# BATT_DISP_v6.net
KiCad netlist of a schematic drawn in EAGLE
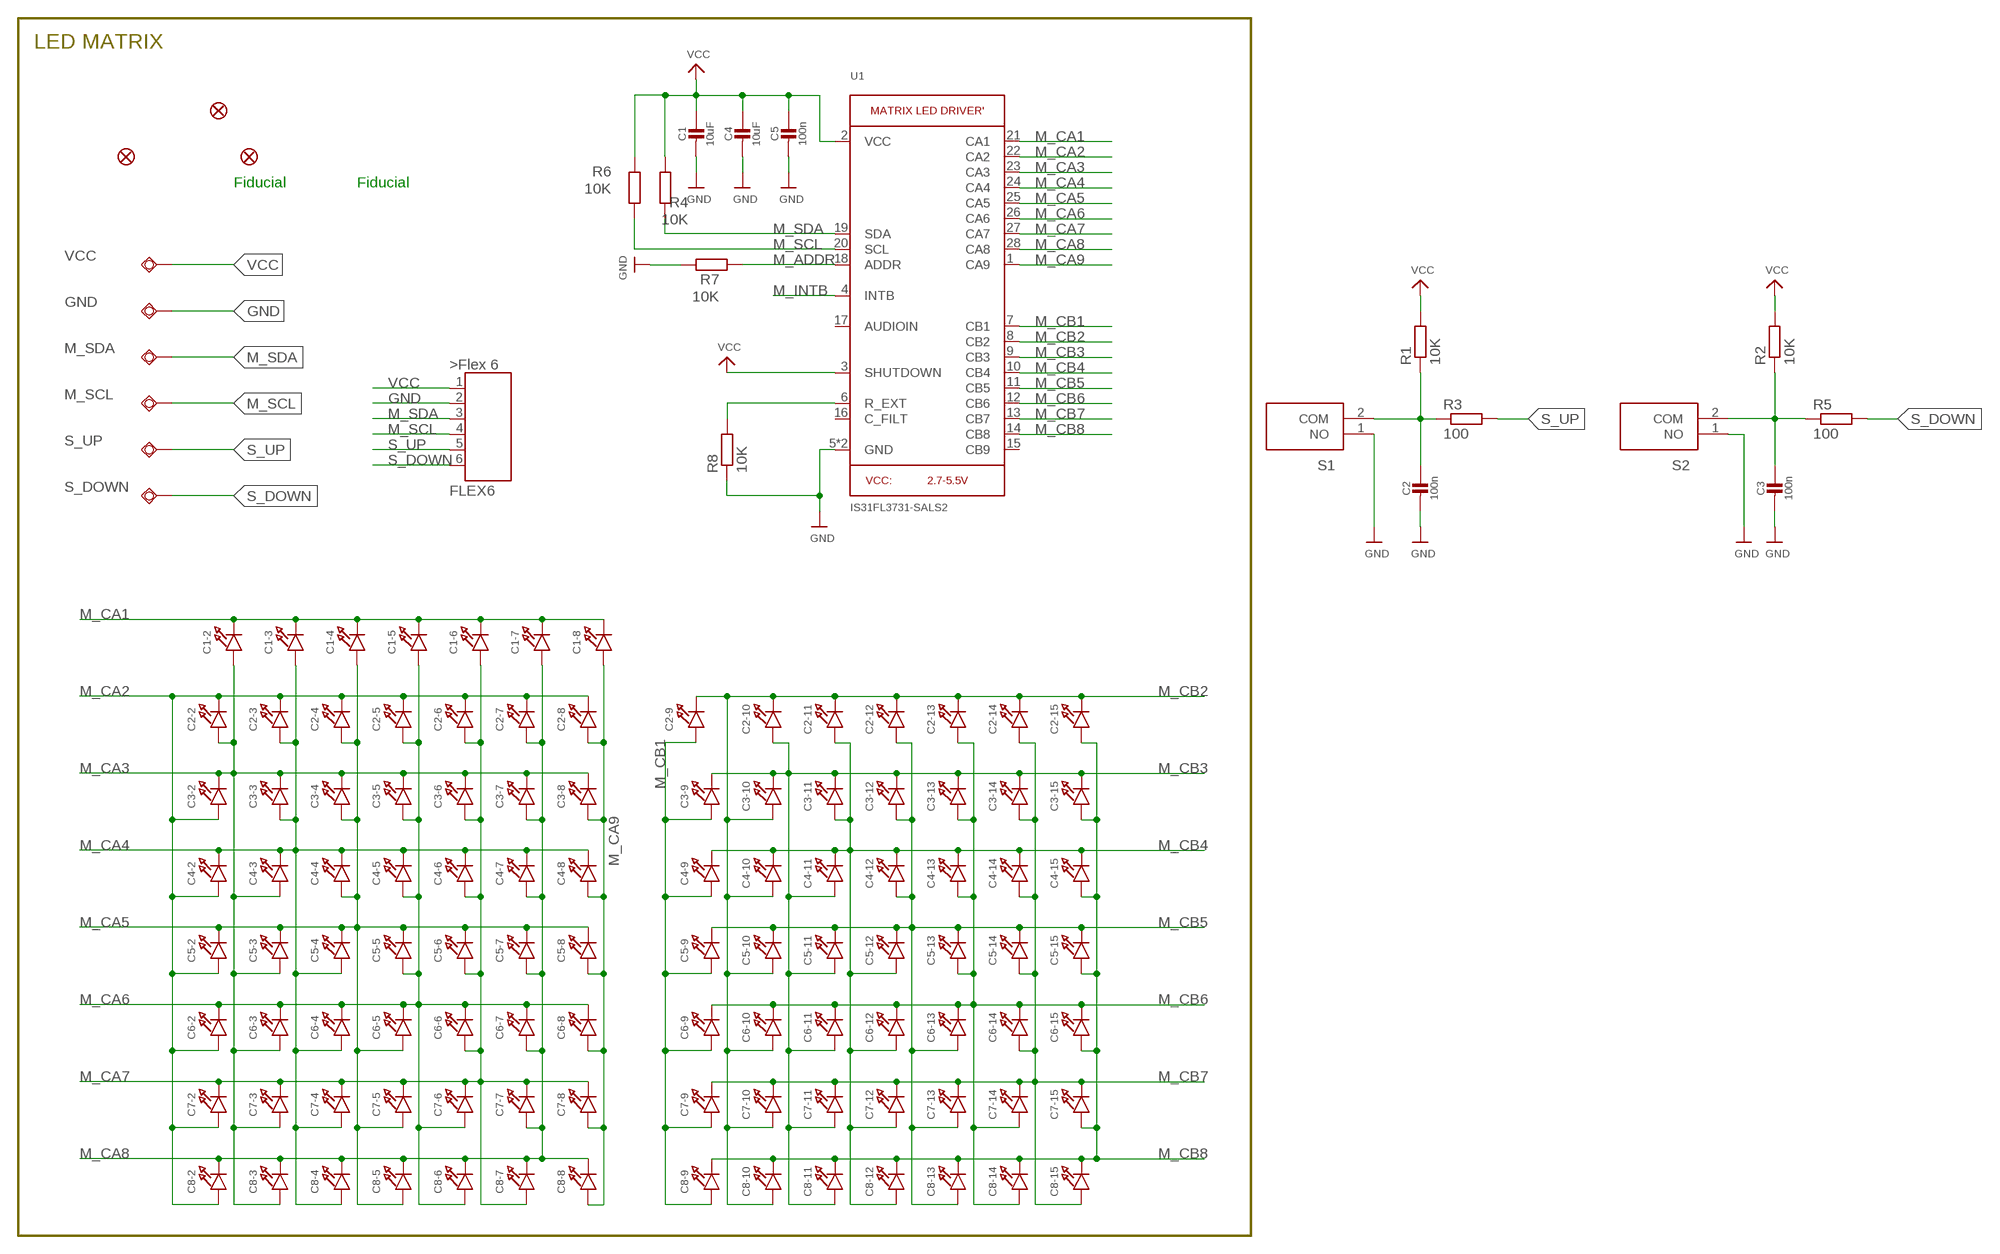
[diagram p0: schematic, sheet 1]

(export (version "E")
  (design (tool "Eeschema 10.0.6"))
  (components
    (comp (ref "C1")
      (value "10uF")
      (footprint "eagle-import:0805-NO")
      (libsource (lib "eagle-import") (part "CAP_CERAMIC0805-NOOUTLINE"))
    )
    (comp (ref "C1-2")
      (value "LED0402_NOOUTLINE")
      (footprint "eagle-import:CHIPLED_0402_NOOUTLINE")
      (libsource (lib "eagle-import") (part "LED0402_NOOUTLINE"))
    )
    (comp (ref "C1-3")
      (value "LED0402_NOOUTLINE")
      (footprint "eagle-import:CHIPLED_0402_NOOUTLINE")
      (libsource (lib "eagle-import") (part "LED0402_NOOUTLINE"))
    )
    (comp (ref "C1-4")
      (value "LED0402_NOOUTLINE")
      (footprint "eagle-import:CHIPLED_0402_NOOUTLINE")
      (libsource (lib "eagle-import") (part "LED0402_NOOUTLINE"))
    )
    (comp (ref "C1-5")
      (value "LED0402_NOOUTLINE")
      (footprint "eagle-import:CHIPLED_0402_NOOUTLINE")
      (libsource (lib "eagle-import") (part "LED0402_NOOUTLINE"))
    )
    (comp (ref "C1-6")
      (value "LED0402_NOOUTLINE")
      (footprint "eagle-import:CHIPLED_0402_NOOUTLINE")
      (libsource (lib "eagle-import") (part "LED0402_NOOUTLINE"))
    )
    (comp (ref "C1-7")
      (value "LED0402_NOOUTLINE")
      (footprint "eagle-import:CHIPLED_0402_NOOUTLINE")
      (libsource (lib "eagle-import") (part "LED0402_NOOUTLINE"))
    )
    (comp (ref "C1-8")
      (value "LED0402_NOOUTLINE")
      (footprint "eagle-import:CHIPLED_0402_NOOUTLINE")
      (libsource (lib "eagle-import") (part "LED0402_NOOUTLINE"))
    )
    (comp (ref "C2")
      (value "100n")
      (footprint "eagle-import:0805-NO")
      (libsource (lib "eagle-import") (part "CAP_CERAMIC0805-NOOUTLINE"))
    )
    (comp (ref "C2-2")
      (value "LED0402_NOOUTLINE")
      (footprint "eagle-import:CHIPLED_0402_NOOUTLINE")
      (libsource (lib "eagle-import") (part "LED0402_NOOUTLINE"))
    )
    (comp (ref "C2-3")
      (value "LED0402_NOOUTLINE")
      (footprint "eagle-import:CHIPLED_0402_NOOUTLINE")
      (libsource (lib "eagle-import") (part "LED0402_NOOUTLINE"))
    )
    (comp (ref "C2-4")
      (value "LED0402_NOOUTLINE")
      (footprint "eagle-import:CHIPLED_0402_NOOUTLINE")
      (libsource (lib "eagle-import") (part "LED0402_NOOUTLINE"))
    )
    (comp (ref "C2-5")
      (value "LED0402_NOOUTLINE")
      (footprint "eagle-import:CHIPLED_0402_NOOUTLINE")
      (libsource (lib "eagle-import") (part "LED0402_NOOUTLINE"))
    )
    (comp (ref "C2-6")
      (value "LED0402_NOOUTLINE")
      (footprint "eagle-import:CHIPLED_0402_NOOUTLINE")
      (libsource (lib "eagle-import") (part "LED0402_NOOUTLINE"))
    )
    (comp (ref "C2-7")
      (value "LED0402_NOOUTLINE")
      (footprint "eagle-import:CHIPLED_0402_NOOUTLINE")
      (libsource (lib "eagle-import") (part "LED0402_NOOUTLINE"))
    )
    (comp (ref "C2-8")
      (value "LED0402_NOOUTLINE")
      (footprint "eagle-import:CHIPLED_0402_NOOUTLINE")
      (libsource (lib "eagle-import") (part "LED0402_NOOUTLINE"))
    )
    (comp (ref "C2-9")
      (value "LED0402_NOOUTLINE")
      (footprint "eagle-import:CHIPLED_0402_NOOUTLINE")
      (libsource (lib "eagle-import") (part "LED0402_NOOUTLINE"))
    )
    (comp (ref "C2-10")
      (value "LED0402_NOOUTLINE")
      (footprint "eagle-import:CHIPLED_0402_NOOUTLINE")
      (libsource (lib "eagle-import") (part "LED0402_NOOUTLINE"))
    )
    (comp (ref "C2-11")
      (value "LED0402_NOOUTLINE")
      (footprint "eagle-import:CHIPLED_0402_NOOUTLINE")
      (libsource (lib "eagle-import") (part "LED0402_NOOUTLINE"))
    )
    (comp (ref "C2-12")
      (value "LED0402_NOOUTLINE")
      (footprint "eagle-import:CHIPLED_0402_NOOUTLINE")
      (libsource (lib "eagle-import") (part "LED0402_NOOUTLINE"))
    )
    (comp (ref "C2-13")
      (value "LED0402_NOOUTLINE")
      (footprint "eagle-import:CHIPLED_0402_NOOUTLINE")
      (libsource (lib "eagle-import") (part "LED0402_NOOUTLINE"))
    )
    (comp (ref "C2-14")
      (value "LED0402_NOOUTLINE")
      (footprint "eagle-import:CHIPLED_0402_NOOUTLINE")
      (libsource (lib "eagle-import") (part "LED0402_NOOUTLINE"))
    )
    (comp (ref "C2-15")
      (value "LED0402_NOOUTLINE")
      (footprint "eagle-import:CHIPLED_0402_NOOUTLINE")
      (libsource (lib "eagle-import") (part "LED0402_NOOUTLINE"))
    )
    (comp (ref "C3")
      (value "100n")
      (footprint "eagle-import:0805-NO")
      (libsource (lib "eagle-import") (part "CAP_CERAMIC0805-NOOUTLINE"))
    )
    (comp (ref "C3-2")
      (value "LED0402_NOOUTLINE")
      (footprint "eagle-import:CHIPLED_0402_NOOUTLINE")
      (libsource (lib "eagle-import") (part "LED0402_NOOUTLINE"))
    )
    (comp (ref "C3-3")
      (value "LED0402_NOOUTLINE")
      (footprint "eagle-import:CHIPLED_0402_NOOUTLINE")
      (libsource (lib "eagle-import") (part "LED0402_NOOUTLINE"))
    )
    (comp (ref "C3-4")
      (value "LED0402_NOOUTLINE")
      (footprint "eagle-import:CHIPLED_0402_NOOUTLINE")
      (libsource (lib "eagle-import") (part "LED0402_NOOUTLINE"))
    )
    (comp (ref "C3-5")
      (value "LED0402_NOOUTLINE")
      (footprint "eagle-import:CHIPLED_0402_NOOUTLINE")
      (libsource (lib "eagle-import") (part "LED0402_NOOUTLINE"))
    )
    (comp (ref "C3-6")
      (value "LED0402_NOOUTLINE")
      (footprint "eagle-import:CHIPLED_0402_NOOUTLINE")
      (libsource (lib "eagle-import") (part "LED0402_NOOUTLINE"))
    )
    (comp (ref "C3-7")
      (value "LED0402_NOOUTLINE")
      (footprint "eagle-import:CHIPLED_0402_NOOUTLINE")
      (libsource (lib "eagle-import") (part "LED0402_NOOUTLINE"))
    )
    (comp (ref "C3-8")
      (value "LED0402_NOOUTLINE")
      (footprint "eagle-import:CHIPLED_0402_NOOUTLINE")
      (libsource (lib "eagle-import") (part "LED0402_NOOUTLINE"))
    )
    (comp (ref "C3-9")
      (value "LED0402_NOOUTLINE")
      (footprint "eagle-import:CHIPLED_0402_NOOUTLINE")
      (libsource (lib "eagle-import") (part "LED0402_NOOUTLINE"))
    )
    (comp (ref "C3-10")
      (value "LED0402_NOOUTLINE")
      (footprint "eagle-import:CHIPLED_0402_NOOUTLINE")
      (libsource (lib "eagle-import") (part "LED0402_NOOUTLINE"))
    )
    (comp (ref "C3-11")
      (value "LED0402_NOOUTLINE")
      (footprint "eagle-import:CHIPLED_0402_NOOUTLINE")
      (libsource (lib "eagle-import") (part "LED0402_NOOUTLINE"))
    )
    (comp (ref "C3-12")
      (value "LED0402_NOOUTLINE")
      (footprint "eagle-import:CHIPLED_0402_NOOUTLINE")
      (libsource (lib "eagle-import") (part "LED0402_NOOUTLINE"))
    )
    (comp (ref "C3-13")
      (value "LED0402_NOOUTLINE")
      (footprint "eagle-import:CHIPLED_0402_NOOUTLINE")
      (libsource (lib "eagle-import") (part "LED0402_NOOUTLINE"))
    )
    (comp (ref "C3-14")
      (value "LED0402_NOOUTLINE")
      (footprint "eagle-import:CHIPLED_0402_NOOUTLINE")
      (libsource (lib "eagle-import") (part "LED0402_NOOUTLINE"))
    )
    (comp (ref "C3-15")
      (value "LED0402_NOOUTLINE")
      (footprint "eagle-import:CHIPLED_0402_NOOUTLINE")
      (libsource (lib "eagle-import") (part "LED0402_NOOUTLINE"))
    )
    (comp (ref "C4")
      (value "10uF")
      (footprint "eagle-import:0805-NO")
      (libsource (lib "eagle-import") (part "CAP_CERAMIC0805-NOOUTLINE"))
    )
    (comp (ref "C4-2")
      (value "LED0402_NOOUTLINE")
      (footprint "eagle-import:CHIPLED_0402_NOOUTLINE")
      (libsource (lib "eagle-import") (part "LED0402_NOOUTLINE"))
    )
    (comp (ref "C4-3")
      (value "LED0402_NOOUTLINE")
      (footprint "eagle-import:CHIPLED_0402_NOOUTLINE")
      (libsource (lib "eagle-import") (part "LED0402_NOOUTLINE"))
    )
    (comp (ref "C4-4")
      (value "LED0402_NOOUTLINE")
      (footprint "eagle-import:CHIPLED_0402_NOOUTLINE")
      (libsource (lib "eagle-import") (part "LED0402_NOOUTLINE"))
    )
    (comp (ref "C4-5")
      (value "LED0402_NOOUTLINE")
      (footprint "eagle-import:CHIPLED_0402_NOOUTLINE")
      (libsource (lib "eagle-import") (part "LED0402_NOOUTLINE"))
    )
    (comp (ref "C4-6")
      (value "LED0402_NOOUTLINE")
      (footprint "eagle-import:CHIPLED_0402_NOOUTLINE")
      (libsource (lib "eagle-import") (part "LED0402_NOOUTLINE"))
    )
    (comp (ref "C4-7")
      (value "LED0402_NOOUTLINE")
      (footprint "eagle-import:CHIPLED_0402_NOOUTLINE")
      (libsource (lib "eagle-import") (part "LED0402_NOOUTLINE"))
    )
    (comp (ref "C4-8")
      (value "LED0402_NOOUTLINE")
      (footprint "eagle-import:CHIPLED_0402_NOOUTLINE")
      (libsource (lib "eagle-import") (part "LED0402_NOOUTLINE"))
    )
    (comp (ref "C4-9")
      (value "LED0402_NOOUTLINE")
      (footprint "eagle-import:CHIPLED_0402_NOOUTLINE")
      (libsource (lib "eagle-import") (part "LED0402_NOOUTLINE"))
    )
    (comp (ref "C4-10")
      (value "LED0402_NOOUTLINE")
      (footprint "eagle-import:CHIPLED_0402_NOOUTLINE")
      (libsource (lib "eagle-import") (part "LED0402_NOOUTLINE"))
    )
    (comp (ref "C4-11")
      (value "LED0402_NOOUTLINE")
      (footprint "eagle-import:CHIPLED_0402_NOOUTLINE")
      (libsource (lib "eagle-import") (part "LED0402_NOOUTLINE"))
    )
    (comp (ref "C4-12")
      (value "LED0402_NOOUTLINE")
      (footprint "eagle-import:CHIPLED_0402_NOOUTLINE")
      (libsource (lib "eagle-import") (part "LED0402_NOOUTLINE"))
    )
    (comp (ref "C4-13")
      (value "LED0402_NOOUTLINE")
      (footprint "eagle-import:CHIPLED_0402_NOOUTLINE")
      (libsource (lib "eagle-import") (part "LED0402_NOOUTLINE"))
    )
    (comp (ref "C4-14")
      (value "LED0402_NOOUTLINE")
      (footprint "eagle-import:CHIPLED_0402_NOOUTLINE")
      (libsource (lib "eagle-import") (part "LED0402_NOOUTLINE"))
    )
    (comp (ref "C4-15")
      (value "LED0402_NOOUTLINE")
      (footprint "eagle-import:CHIPLED_0402_NOOUTLINE")
      (libsource (lib "eagle-import") (part "LED0402_NOOUTLINE"))
    )
    (comp (ref "C5")
      (value "100n")
      (footprint "eagle-import:0805-NO")
      (libsource (lib "eagle-import") (part "CAP_CERAMIC0805-NOOUTLINE"))
    )
    (comp (ref "C5-2")
      (value "LED0402_NOOUTLINE")
      (footprint "eagle-import:CHIPLED_0402_NOOUTLINE")
      (libsource (lib "eagle-import") (part "LED0402_NOOUTLINE"))
    )
    (comp (ref "C5-3")
      (value "LED0402_NOOUTLINE")
      (footprint "eagle-import:CHIPLED_0402_NOOUTLINE")
      (libsource (lib "eagle-import") (part "LED0402_NOOUTLINE"))
    )
    (comp (ref "C5-4")
      (value "LED0402_NOOUTLINE")
      (footprint "eagle-import:CHIPLED_0402_NOOUTLINE")
      (libsource (lib "eagle-import") (part "LED0402_NOOUTLINE"))
    )
    (comp (ref "C5-5")
      (value "LED0402_NOOUTLINE")
      (footprint "eagle-import:CHIPLED_0402_NOOUTLINE")
      (libsource (lib "eagle-import") (part "LED0402_NOOUTLINE"))
    )
    (comp (ref "C5-6")
      (value "LED0402_NOOUTLINE")
      (footprint "eagle-import:CHIPLED_0402_NOOUTLINE")
      (libsource (lib "eagle-import") (part "LED0402_NOOUTLINE"))
    )
    (comp (ref "C5-7")
      (value "LED0402_NOOUTLINE")
      (footprint "eagle-import:CHIPLED_0402_NOOUTLINE")
      (libsource (lib "eagle-import") (part "LED0402_NOOUTLINE"))
    )
    (comp (ref "C5-8")
      (value "LED0402_NOOUTLINE")
      (footprint "eagle-import:CHIPLED_0402_NOOUTLINE")
      (libsource (lib "eagle-import") (part "LED0402_NOOUTLINE"))
    )
    (comp (ref "C5-9")
      (value "LED0402_NOOUTLINE")
      (footprint "eagle-import:CHIPLED_0402_NOOUTLINE")
      (libsource (lib "eagle-import") (part "LED0402_NOOUTLINE"))
    )
    (comp (ref "C5-10")
      (value "LED0402_NOOUTLINE")
      (footprint "eagle-import:CHIPLED_0402_NOOUTLINE")
      (libsource (lib "eagle-import") (part "LED0402_NOOUTLINE"))
    )
    (comp (ref "C5-11")
      (value "LED0402_NOOUTLINE")
      (footprint "eagle-import:CHIPLED_0402_NOOUTLINE")
      (libsource (lib "eagle-import") (part "LED0402_NOOUTLINE"))
    )
    (comp (ref "C5-12")
      (value "LED0402_NOOUTLINE")
      (footprint "eagle-import:CHIPLED_0402_NOOUTLINE")
      (libsource (lib "eagle-import") (part "LED0402_NOOUTLINE"))
    )
    (comp (ref "C5-13")
      (value "LED0402_NOOUTLINE")
      (footprint "eagle-import:CHIPLED_0402_NOOUTLINE")
      (libsource (lib "eagle-import") (part "LED0402_NOOUTLINE"))
    )
    (comp (ref "C5-14")
      (value "LED0402_NOOUTLINE")
      (footprint "eagle-import:CHIPLED_0402_NOOUTLINE")
      (libsource (lib "eagle-import") (part "LED0402_NOOUTLINE"))
    )
    (comp (ref "C5-15")
      (value "LED0402_NOOUTLINE")
      (footprint "eagle-import:CHIPLED_0402_NOOUTLINE")
      (libsource (lib "eagle-import") (part "LED0402_NOOUTLINE"))
    )
    (comp (ref "C6-2")
      (value "LED0402_NOOUTLINE")
      (footprint "eagle-import:CHIPLED_0402_NOOUTLINE")
      (libsource (lib "eagle-import") (part "LED0402_NOOUTLINE"))
    )
    (comp (ref "C6-3")
      (value "LED0402_NOOUTLINE")
      (footprint "eagle-import:CHIPLED_0402_NOOUTLINE")
      (libsource (lib "eagle-import") (part "LED0402_NOOUTLINE"))
    )
    (comp (ref "C6-4")
      (value "LED0402_NOOUTLINE")
      (footprint "eagle-import:CHIPLED_0402_NOOUTLINE")
      (libsource (lib "eagle-import") (part "LED0402_NOOUTLINE"))
    )
    (comp (ref "C6-5")
      (value "LED0402_NOOUTLINE")
      (footprint "eagle-import:CHIPLED_0402_NOOUTLINE")
      (libsource (lib "eagle-import") (part "LED0402_NOOUTLINE"))
    )
    (comp (ref "C6-6")
      (value "LED0402_NOOUTLINE")
      (footprint "eagle-import:CHIPLED_0402_NOOUTLINE")
      (libsource (lib "eagle-import") (part "LED0402_NOOUTLINE"))
    )
    (comp (ref "C6-7")
      (value "LED0402_NOOUTLINE")
      (footprint "eagle-import:CHIPLED_0402_NOOUTLINE")
      (libsource (lib "eagle-import") (part "LED0402_NOOUTLINE"))
    )
    (comp (ref "C6-8")
      (value "LED0402_NOOUTLINE")
      (footprint "eagle-import:CHIPLED_0402_NOOUTLINE")
      (libsource (lib "eagle-import") (part "LED0402_NOOUTLINE"))
    )
    (comp (ref "C6-9")
      (value "LED0402_NOOUTLINE")
      (footprint "eagle-import:CHIPLED_0402_NOOUTLINE")
      (libsource (lib "eagle-import") (part "LED0402_NOOUTLINE"))
    )
    (comp (ref "C6-10")
      (value "LED0402_NOOUTLINE")
      (footprint "eagle-import:CHIPLED_0402_NOOUTLINE")
      (libsource (lib "eagle-import") (part "LED0402_NOOUTLINE"))
    )
    (comp (ref "C6-11")
      (value "LED0402_NOOUTLINE")
      (footprint "eagle-import:CHIPLED_0402_NOOUTLINE")
      (libsource (lib "eagle-import") (part "LED0402_NOOUTLINE"))
    )
    (comp (ref "C6-12")
      (value "LED0402_NOOUTLINE")
      (footprint "eagle-import:CHIPLED_0402_NOOUTLINE")
      (libsource (lib "eagle-import") (part "LED0402_NOOUTLINE"))
    )
    (comp (ref "C6-13")
      (value "LED0402_NOOUTLINE")
      (footprint "eagle-import:CHIPLED_0402_NOOUTLINE")
      (libsource (lib "eagle-import") (part "LED0402_NOOUTLINE"))
    )
    (comp (ref "C6-14")
      (value "LED0402_NOOUTLINE")
      (footprint "eagle-import:CHIPLED_0402_NOOUTLINE")
      (libsource (lib "eagle-import") (part "LED0402_NOOUTLINE"))
    )
    (comp (ref "C6-15")
      (value "LED0402_NOOUTLINE")
      (footprint "eagle-import:CHIPLED_0402_NOOUTLINE")
      (libsource (lib "eagle-import") (part "LED0402_NOOUTLINE"))
    )
    (comp (ref "C7-2")
      (value "LED0402_NOOUTLINE")
      (footprint "eagle-import:CHIPLED_0402_NOOUTLINE")
      (libsource (lib "eagle-import") (part "LED0402_NOOUTLINE"))
    )
    (comp (ref "C7-3")
      (value "LED0402_NOOUTLINE")
      (footprint "eagle-import:CHIPLED_0402_NOOUTLINE")
      (libsource (lib "eagle-import") (part "LED0402_NOOUTLINE"))
    )
    (comp (ref "C7-4")
      (value "LED0402_NOOUTLINE")
      (footprint "eagle-import:CHIPLED_0402_NOOUTLINE")
      (libsource (lib "eagle-import") (part "LED0402_NOOUTLINE"))
    )
    (comp (ref "C7-5")
      (value "LED0402_NOOUTLINE")
      (footprint "eagle-import:CHIPLED_0402_NOOUTLINE")
      (libsource (lib "eagle-import") (part "LED0402_NOOUTLINE"))
    )
    (comp (ref "C7-6")
      (value "LED0402_NOOUTLINE")
      (footprint "eagle-import:CHIPLED_0402_NOOUTLINE")
      (libsource (lib "eagle-import") (part "LED0402_NOOUTLINE"))
    )
    (comp (ref "C7-7")
      (value "LED0402_NOOUTLINE")
      (footprint "eagle-import:CHIPLED_0402_NOOUTLINE")
      (libsource (lib "eagle-import") (part "LED0402_NOOUTLINE"))
    )
    (comp (ref "C7-8")
      (value "LED0402_NOOUTLINE")
      (footprint "eagle-import:CHIPLED_0402_NOOUTLINE")
      (libsource (lib "eagle-import") (part "LED0402_NOOUTLINE"))
    )
    (comp (ref "C7-9")
      (value "LED0402_NOOUTLINE")
      (footprint "eagle-import:CHIPLED_0402_NOOUTLINE")
      (libsource (lib "eagle-import") (part "LED0402_NOOUTLINE"))
    )
    (comp (ref "C7-10")
      (value "LED0402_NOOUTLINE")
      (footprint "eagle-import:CHIPLED_0402_NOOUTLINE")
      (libsource (lib "eagle-import") (part "LED0402_NOOUTLINE"))
    )
    (comp (ref "C7-11")
      (value "LED0402_NOOUTLINE")
      (footprint "eagle-import:CHIPLED_0402_NOOUTLINE")
      (libsource (lib "eagle-import") (part "LED0402_NOOUTLINE"))
    )
    (comp (ref "C7-12")
      (value "LED0402_NOOUTLINE")
      (footprint "eagle-import:CHIPLED_0402_NOOUTLINE")
      (libsource (lib "eagle-import") (part "LED0402_NOOUTLINE"))
    )
    (comp (ref "C7-13")
      (value "LED0402_NOOUTLINE")
      (footprint "eagle-import:CHIPLED_0402_NOOUTLINE")
      (libsource (lib "eagle-import") (part "LED0402_NOOUTLINE"))
    )
    (comp (ref "C7-14")
      (value "LED0402_NOOUTLINE")
      (footprint "eagle-import:CHIPLED_0402_NOOUTLINE")
      (libsource (lib "eagle-import") (part "LED0402_NOOUTLINE"))
    )
    (comp (ref "C7-15")
      (value "LED0402_NOOUTLINE")
      (footprint "eagle-import:CHIPLED_0402_NOOUTLINE")
      (libsource (lib "eagle-import") (part "LED0402_NOOUTLINE"))
    )
    (comp (ref "C8-2")
      (value "LED0402_NOOUTLINE")
      (footprint "eagle-import:CHIPLED_0402_NOOUTLINE")
      (libsource (lib "eagle-import") (part "LED0402_NOOUTLINE"))
    )
    (comp (ref "C8-3")
      (value "LED0402_NOOUTLINE")
      (footprint "eagle-import:CHIPLED_0402_NOOUTLINE")
      (libsource (lib "eagle-import") (part "LED0402_NOOUTLINE"))
    )
    (comp (ref "C8-4")
      (value "LED0402_NOOUTLINE")
      (footprint "eagle-import:CHIPLED_0402_NOOUTLINE")
      (libsource (lib "eagle-import") (part "LED0402_NOOUTLINE"))
    )
    (comp (ref "C8-5")
      (value "LED0402_NOOUTLINE")
      (footprint "eagle-import:CHIPLED_0402_NOOUTLINE")
      (libsource (lib "eagle-import") (part "LED0402_NOOUTLINE"))
    )
    (comp (ref "C8-6")
      (value "LED0402_NOOUTLINE")
      (footprint "eagle-import:CHIPLED_0402_NOOUTLINE")
      (libsource (lib "eagle-import") (part "LED0402_NOOUTLINE"))
    )
    (comp (ref "C8-7")
      (value "LED0402_NOOUTLINE")
      (footprint "eagle-import:CHIPLED_0402_NOOUTLINE")
      (libsource (lib "eagle-import") (part "LED0402_NOOUTLINE"))
    )
    (comp (ref "C8-8")
      (value "LED0402_NOOUTLINE")
      (footprint "eagle-import:CHIPLED_0402_NOOUTLINE")
      (libsource (lib "eagle-import") (part "LED0402_NOOUTLINE"))
    )
    (comp (ref "C8-9")
      (value "LED0402_NOOUTLINE")
      (footprint "eagle-import:CHIPLED_0402_NOOUTLINE")
      (libsource (lib "eagle-import") (part "LED0402_NOOUTLINE"))
    )
    (comp (ref "C8-10")
      (value "LED0402_NOOUTLINE")
      (footprint "eagle-import:CHIPLED_0402_NOOUTLINE")
      (libsource (lib "eagle-import") (part "LED0402_NOOUTLINE"))
    )
    (comp (ref "C8-11")
      (value "LED0402_NOOUTLINE")
      (footprint "eagle-import:CHIPLED_0402_NOOUTLINE")
      (libsource (lib "eagle-import") (part "LED0402_NOOUTLINE"))
    )
    (comp (ref "C8-12")
      (value "LED0402_NOOUTLINE")
      (footprint "eagle-import:CHIPLED_0402_NOOUTLINE")
      (libsource (lib "eagle-import") (part "LED0402_NOOUTLINE"))
    )
    (comp (ref "C8-13")
      (value "LED0402_NOOUTLINE")
      (footprint "eagle-import:CHIPLED_0402_NOOUTLINE")
      (libsource (lib "eagle-import") (part "LED0402_NOOUTLINE"))
    )
    (comp (ref "C8-14")
      (value "LED0402_NOOUTLINE")
      (footprint "eagle-import:CHIPLED_0402_NOOUTLINE")
      (libsource (lib "eagle-import") (part "LED0402_NOOUTLINE"))
    )
    (comp (ref "C8-15")
      (value "LED0402_NOOUTLINE")
      (footprint "eagle-import:CHIPLED_0402_NOOUTLINE")
      (libsource (lib "eagle-import") (part "LED0402_NOOUTLINE"))
    )
    (comp (ref "FD1")
      (value "FIDUCIALUFIDUCIAL")
      (footprint "eagle-import:FIDUCIAL-MICRO")
      (libsource (lib "eagle-import") (part "FIDUCIALUFIDUCIAL"))
    )
    (comp (ref "FD2")
      (value "FIDUCIAL\"\"")
      (footprint "eagle-import:FIDUCIAL_1MM")
      (libsource (lib "eagle-import") (part "FIDUCIAL{dblquote}{dblquote}"))
    )
    (comp (ref "FD3")
      (value "FIDUCIAL\"\"")
      (footprint "eagle-import:FIDUCIAL_1MM")
      (libsource (lib "eagle-import") (part "FIDUCIAL{dblquote}{dblquote}"))
    )
    (comp (ref "GND")
      (value "TESTPAD_TPSQB1,27")
      (footprint "eagle-import:TESTPAD_B1,27")
      (libsource (lib "eagle-import") (part "TESTPAD_TPSQB1,27"))
    )
    (comp (ref "K1")
      (value "FLEX6")
      (footprint "eagle-import:FLEX6")
      (libsource (lib "eagle-import") (part "FLEX6"))
    )
    (comp (ref "M_SCL")
      (value "TESTPAD_TPSQB1,27")
      (footprint "eagle-import:TESTPAD_B1,27")
      (libsource (lib "eagle-import") (part "TESTPAD_TPSQB1,27"))
    )
    (comp (ref "M_SDA")
      (value "TESTPAD_TPSQB1,27")
      (footprint "eagle-import:TESTPAD_B1,27")
      (libsource (lib "eagle-import") (part "TESTPAD_TPSQB1,27"))
    )
    (comp (ref "R1")
      (value "10K")
      (footprint "eagle-import:R0603")
      (libsource (lib "eagle-import") (part "R-EU_R0603"))
    )
    (comp (ref "R2")
      (value "10K")
      (footprint "eagle-import:R0603")
      (libsource (lib "eagle-import") (part "R-EU_R0603"))
    )
    (comp (ref "R3")
      (value "100")
      (footprint "eagle-import:R0603")
      (libsource (lib "eagle-import") (part "R-EU_R0603"))
    )
    (comp (ref "R4")
      (value "10K")
      (footprint "eagle-import:R0603")
      (libsource (lib "eagle-import") (part "R-EU_R0603"))
    )
    (comp (ref "R5")
      (value "100")
      (footprint "eagle-import:R0603")
      (libsource (lib "eagle-import") (part "R-EU_R0603"))
    )
    (comp (ref "R6")
      (value "10K")
      (footprint "eagle-import:R0603")
      (libsource (lib "eagle-import") (part "R-EU_R0603"))
    )
    (comp (ref "R7")
      (value "10K")
      (footprint "eagle-import:R0603")
      (libsource (lib "eagle-import") (part "R-EU_R0603"))
    )
    (comp (ref "R8")
      (value "10K")
      (footprint "eagle-import:R0603")
      (libsource (lib "eagle-import") (part "R-EU_R0603"))
    )
    (comp (ref "S1")
      (value "KXT311LHS")
      (footprint "eagle-import:KXT311LHS")
      (fields (field (name "MOUSER_PART_NUMBER") "611-KXT311LHS"))
      (libsource (lib "eagle-import") (part "KXT311LHS"))
    )
    (comp (ref "S2")
      (value "KXT311LHS")
      (footprint "eagle-import:KXT311LHS")
      (fields (field (name "MOUSER_PART_NUMBER") "611-KXT311LHS"))
      (libsource (lib "eagle-import") (part "KXT311LHS"))
    )
    (comp (ref "S_DOWN")
      (value "TESTPAD_TPSQB1,27")
      (footprint "eagle-import:TESTPAD_B1,27")
      (libsource (lib "eagle-import") (part "TESTPAD_TPSQB1,27"))
    )
    (comp (ref "S_UP")
      (value "TESTPAD_TPSQB1,27")
      (footprint "eagle-import:TESTPAD_B1,27")
      (libsource (lib "eagle-import") (part "TESTPAD_TPSQB1,27"))
    )
    (comp (ref "U1")
      (value "IS31FL3731-SALS2")
      (footprint "eagle-import:QFN28_4MM_0.4MM")
      (libsource (lib "eagle-import") (part "IS31FL3731QFN"))
    )
    (comp (ref "VCC")
      (value "TESTPAD_TPSQB1,27")
      (footprint "eagle-import:TESTPAD_B1,27")
      (libsource (lib "eagle-import") (part "TESTPAD_TPSQB1,27"))
    )
  )
  (nets
    (net (code "1") (name "/M_ADDR") (class "Default")
      (node (ref "R7") (pin "1") (pinfunction "1_1") (pintype "passive"))
      (node (ref "U1") (pin "18") (pinfunction "ADDR_18") (pintype "bidirectional"))
    )
    (net (code "2") (name "/M_CA1") (class "Default")
      (node (ref "C1-2") (pin "C") (pinfunction "C_C") (pintype "passive"))
      (node (ref "C1-3") (pin "C") (pinfunction "C_C") (pintype "passive"))
      (node (ref "C1-4") (pin "C") (pinfunction "C_C") (pintype "passive"))
      (node (ref "C1-5") (pin "C") (pinfunction "C_C") (pintype "passive"))
      (node (ref "C1-6") (pin "C") (pinfunction "C_C") (pintype "passive"))
      (node (ref "C1-7") (pin "C") (pinfunction "C_C") (pintype "passive"))
      (node (ref "C1-8") (pin "C") (pinfunction "C_C") (pintype "passive"))
      (node (ref "U1") (pin "21") (pinfunction "CA1_21") (pintype "bidirectional"))
    )
    (net (code "3") (name "/M_CA2") (class "Default")
      (node (ref "C2-2") (pin "C") (pinfunction "C_C") (pintype "passive"))
      (node (ref "C2-3") (pin "C") (pinfunction "C_C") (pintype "passive"))
      (node (ref "C2-4") (pin "C") (pinfunction "C_C") (pintype "passive"))
      (node (ref "C2-5") (pin "C") (pinfunction "C_C") (pintype "passive"))
      (node (ref "C2-6") (pin "C") (pinfunction "C_C") (pintype "passive"))
      (node (ref "C2-7") (pin "C") (pinfunction "C_C") (pintype "passive"))
      (node (ref "C2-8") (pin "C") (pinfunction "C_C") (pintype "passive"))
      (node (ref "C3-2") (pin "A") (pinfunction "A_A") (pintype "passive"))
      (node (ref "C4-2") (pin "A") (pinfunction "A_A") (pintype "passive"))
      (node (ref "C5-2") (pin "A") (pinfunction "A_A") (pintype "passive"))
      (node (ref "C6-2") (pin "A") (pinfunction "A_A") (pintype "passive"))
      (node (ref "C7-2") (pin "A") (pinfunction "A_A") (pintype "passive"))
      (node (ref "C8-2") (pin "A") (pinfunction "A_A") (pintype "passive"))
      (node (ref "U1") (pin "22") (pinfunction "CA2_22") (pintype "bidirectional"))
    )
    (net (code "4") (name "/M_CA3") (class "Default")
      (node (ref "C1-2") (pin "A") (pinfunction "A_A") (pintype "passive"))
      (node (ref "C2-2") (pin "A") (pinfunction "A_A") (pintype "passive"))
      (node (ref "C3-2") (pin "C") (pinfunction "C_C") (pintype "passive"))
      (node (ref "C3-3") (pin "C") (pinfunction "C_C") (pintype "passive"))
      (node (ref "C3-4") (pin "C") (pinfunction "C_C") (pintype "passive"))
      (node (ref "C3-5") (pin "C") (pinfunction "C_C") (pintype "passive"))
      (node (ref "C3-6") (pin "C") (pinfunction "C_C") (pintype "passive"))
      (node (ref "C3-7") (pin "C") (pinfunction "C_C") (pintype "passive"))
      (node (ref "C3-8") (pin "C") (pinfunction "C_C") (pintype "passive"))
      (node (ref "C4-3") (pin "A") (pinfunction "A_A") (pintype "passive"))
      (node (ref "C5-3") (pin "A") (pinfunction "A_A") (pintype "passive"))
      (node (ref "C6-3") (pin "A") (pinfunction "A_A") (pintype "passive"))
      (node (ref "C7-3") (pin "A") (pinfunction "A_A") (pintype "passive"))
      (node (ref "C8-3") (pin "A") (pinfunction "A_A") (pintype "passive"))
      (node (ref "U1") (pin "23") (pinfunction "CA3_23") (pintype "bidirectional"))
    )
    (net (code "5") (name "/M_CA4") (class "Default")
      (node (ref "C1-3") (pin "A") (pinfunction "A_A") (pintype "passive"))
      (node (ref "C2-3") (pin "A") (pinfunction "A_A") (pintype "passive"))
      (node (ref "C3-3") (pin "A") (pinfunction "A_A") (pintype "passive"))
      (node (ref "C4-2") (pin "C") (pinfunction "C_C") (pintype "passive"))
      (node (ref "C4-3") (pin "C") (pinfunction "C_C") (pintype "passive"))
      (node (ref "C4-4") (pin "C") (pinfunction "C_C") (pintype "passive"))
      (node (ref "C4-5") (pin "C") (pinfunction "C_C") (pintype "passive"))
      (node (ref "C4-6") (pin "C") (pinfunction "C_C") (pintype "passive"))
      (node (ref "C4-7") (pin "C") (pinfunction "C_C") (pintype "passive"))
      (node (ref "C4-8") (pin "C") (pinfunction "C_C") (pintype "passive"))
      (node (ref "C5-4") (pin "A") (pinfunction "A_A") (pintype "passive"))
      (node (ref "C6-4") (pin "A") (pinfunction "A_A") (pintype "passive"))
      (node (ref "C7-4") (pin "A") (pinfunction "A_A") (pintype "passive"))
      (node (ref "C8-4") (pin "A") (pinfunction "A_A") (pintype "passive"))
      (node (ref "U1") (pin "24") (pinfunction "CA4_24") (pintype "bidirectional"))
    )
    (net (code "6") (name "/M_CA5") (class "Default")
      (node (ref "C1-4") (pin "A") (pinfunction "A_A") (pintype "passive"))
      (node (ref "C2-4") (pin "A") (pinfunction "A_A") (pintype "passive"))
      (node (ref "C3-4") (pin "A") (pinfunction "A_A") (pintype "passive"))
      (node (ref "C4-4") (pin "A") (pinfunction "A_A") (pintype "passive"))
      (node (ref "C5-2") (pin "C") (pinfunction "C_C") (pintype "passive"))
      (node (ref "C5-3") (pin "C") (pinfunction "C_C") (pintype "passive"))
      (node (ref "C5-4") (pin "C") (pinfunction "C_C") (pintype "passive"))
      (node (ref "C5-5") (pin "C") (pinfunction "C_C") (pintype "passive"))
      (node (ref "C5-6") (pin "C") (pinfunction "C_C") (pintype "passive"))
      (node (ref "C5-7") (pin "C") (pinfunction "C_C") (pintype "passive"))
      (node (ref "C5-8") (pin "C") (pinfunction "C_C") (pintype "passive"))
      (node (ref "C6-5") (pin "A") (pinfunction "A_A") (pintype "passive"))
      (node (ref "C7-5") (pin "A") (pinfunction "A_A") (pintype "passive"))
      (node (ref "C8-5") (pin "A") (pinfunction "A_A") (pintype "passive"))
      (node (ref "U1") (pin "25") (pinfunction "CA5_25") (pintype "bidirectional"))
    )
    (net (code "7") (name "/M_CA6") (class "Default")
      (node (ref "C1-5") (pin "A") (pinfunction "A_A") (pintype "passive"))
      (node (ref "C2-5") (pin "A") (pinfunction "A_A") (pintype "passive"))
      (node (ref "C3-5") (pin "A") (pinfunction "A_A") (pintype "passive"))
      (node (ref "C4-5") (pin "A") (pinfunction "A_A") (pintype "passive"))
      (node (ref "C5-5") (pin "A") (pinfunction "A_A") (pintype "passive"))
      (node (ref "C6-2") (pin "C") (pinfunction "C_C") (pintype "passive"))
      (node (ref "C6-3") (pin "C") (pinfunction "C_C") (pintype "passive"))
      (node (ref "C6-4") (pin "C") (pinfunction "C_C") (pintype "passive"))
      (node (ref "C6-5") (pin "C") (pinfunction "C_C") (pintype "passive"))
      (node (ref "C6-6") (pin "C") (pinfunction "C_C") (pintype "passive"))
      (node (ref "C6-7") (pin "C") (pinfunction "C_C") (pintype "passive"))
      (node (ref "C6-8") (pin "C") (pinfunction "C_C") (pintype "passive"))
      (node (ref "C7-6") (pin "A") (pinfunction "A_A") (pintype "passive"))
      (node (ref "C8-6") (pin "A") (pinfunction "A_A") (pintype "passive"))
      (node (ref "U1") (pin "26") (pinfunction "CA6_26") (pintype "bidirectional"))
    )
    (net (code "8") (name "/M_CA7") (class "Default")
      (node (ref "C1-6") (pin "A") (pinfunction "A_A") (pintype "passive"))
      (node (ref "C2-6") (pin "A") (pinfunction "A_A") (pintype "passive"))
      (node (ref "C3-6") (pin "A") (pinfunction "A_A") (pintype "passive"))
      (node (ref "C4-6") (pin "A") (pinfunction "A_A") (pintype "passive"))
      (node (ref "C5-6") (pin "A") (pinfunction "A_A") (pintype "passive"))
      (node (ref "C6-6") (pin "A") (pinfunction "A_A") (pintype "passive"))
      (node (ref "C7-2") (pin "C") (pinfunction "C_C") (pintype "passive"))
      (node (ref "C7-3") (pin "C") (pinfunction "C_C") (pintype "passive"))
      (node (ref "C7-4") (pin "C") (pinfunction "C_C") (pintype "passive"))
      (node (ref "C7-5") (pin "C") (pinfunction "C_C") (pintype "passive"))
      (node (ref "C7-6") (pin "C") (pinfunction "C_C") (pintype "passive"))
      (node (ref "C7-7") (pin "C") (pinfunction "C_C") (pintype "passive"))
      (node (ref "C7-8") (pin "C") (pinfunction "C_C") (pintype "passive"))
      (node (ref "C8-7") (pin "A") (pinfunction "A_A") (pintype "passive"))
      (node (ref "U1") (pin "27") (pinfunction "CA7_27") (pintype "bidirectional"))
    )
    (net (code "9") (name "/M_CA8") (class "Default")
      (node (ref "C1-7") (pin "A") (pinfunction "A_A") (pintype "passive"))
      (node (ref "C2-7") (pin "A") (pinfunction "A_A") (pintype "passive"))
      (node (ref "C3-7") (pin "A") (pinfunction "A_A") (pintype "passive"))
      (node (ref "C4-7") (pin "A") (pinfunction "A_A") (pintype "passive"))
      (node (ref "C5-7") (pin "A") (pinfunction "A_A") (pintype "passive"))
      (node (ref "C6-7") (pin "A") (pinfunction "A_A") (pintype "passive"))
      (node (ref "C7-7") (pin "A") (pinfunction "A_A") (pintype "passive"))
      (node (ref "C8-2") (pin "C") (pinfunction "C_C") (pintype "passive"))
      (node (ref "C8-3") (pin "C") (pinfunction "C_C") (pintype "passive"))
      (node (ref "C8-4") (pin "C") (pinfunction "C_C") (pintype "passive"))
      (node (ref "C8-5") (pin "C") (pinfunction "C_C") (pintype "passive"))
      (node (ref "C8-6") (pin "C") (pinfunction "C_C") (pintype "passive"))
      (node (ref "C8-7") (pin "C") (pinfunction "C_C") (pintype "passive"))
      (node (ref "C8-8") (pin "C") (pinfunction "C_C") (pintype "passive"))
      (node (ref "U1") (pin "28") (pinfunction "CA8_28") (pintype "bidirectional"))
    )
    (net (code "10") (name "/M_CA9") (class "Default")
      (node (ref "C1-8") (pin "A") (pinfunction "A_A") (pintype "passive"))
      (node (ref "C2-8") (pin "A") (pinfunction "A_A") (pintype "passive"))
      (node (ref "C3-8") (pin "A") (pinfunction "A_A") (pintype "passive"))
      (node (ref "C4-8") (pin "A") (pinfunction "A_A") (pintype "passive"))
      (node (ref "C5-8") (pin "A") (pinfunction "A_A") (pintype "passive"))
      (node (ref "C6-8") (pin "A") (pinfunction "A_A") (pintype "passive"))
      (node (ref "C7-8") (pin "A") (pinfunction "A_A") (pintype "passive"))
      (node (ref "C8-8") (pin "A") (pinfunction "A_A") (pintype "passive"))
      (node (ref "U1") (pin "1") (pinfunction "CA9_1") (pintype "bidirectional"))
    )
    (net (code "11") (name "/M_CB1") (class "Default")
      (node (ref "C2-9") (pin "A") (pinfunction "A_A") (pintype "passive"))
      (node (ref "C3-9") (pin "A") (pinfunction "A_A") (pintype "passive"))
      (node (ref "C4-9") (pin "A") (pinfunction "A_A") (pintype "passive"))
      (node (ref "C5-9") (pin "A") (pinfunction "A_A") (pintype "passive"))
      (node (ref "C6-9") (pin "A") (pinfunction "A_A") (pintype "passive"))
      (node (ref "C7-9") (pin "A") (pinfunction "A_A") (pintype "passive"))
      (node (ref "C8-9") (pin "A") (pinfunction "A_A") (pintype "passive"))
      (node (ref "U1") (pin "7") (pinfunction "CB1_7") (pintype "bidirectional"))
    )
    (net (code "12") (name "/M_CB2") (class "Default")
      (node (ref "C2-10") (pin "C") (pinfunction "C_C") (pintype "passive"))
      (node (ref "C2-11") (pin "C") (pinfunction "C_C") (pintype "passive"))
      (node (ref "C2-12") (pin "C") (pinfunction "C_C") (pintype "passive"))
      (node (ref "C2-13") (pin "C") (pinfunction "C_C") (pintype "passive"))
      (node (ref "C2-14") (pin "C") (pinfunction "C_C") (pintype "passive"))
      (node (ref "C2-15") (pin "C") (pinfunction "C_C") (pintype "passive"))
      (node (ref "C2-9") (pin "C") (pinfunction "C_C") (pintype "passive"))
      (node (ref "C3-10") (pin "A") (pinfunction "A_A") (pintype "passive"))
      (node (ref "C4-10") (pin "A") (pinfunction "A_A") (pintype "passive"))
      (node (ref "C5-10") (pin "A") (pinfunction "A_A") (pintype "passive"))
      (node (ref "C6-10") (pin "A") (pinfunction "A_A") (pintype "passive"))
      (node (ref "C7-10") (pin "A") (pinfunction "A_A") (pintype "passive"))
      (node (ref "C8-10") (pin "A") (pinfunction "A_A") (pintype "passive"))
      (node (ref "U1") (pin "8") (pinfunction "CB2_8") (pintype "bidirectional"))
    )
    (net (code "13") (name "/M_CB3") (class "Default")
      (node (ref "C2-10") (pin "A") (pinfunction "A_A") (pintype "passive"))
      (node (ref "C3-10") (pin "C") (pinfunction "C_C") (pintype "passive"))
      (node (ref "C3-11") (pin "C") (pinfunction "C_C") (pintype "passive"))
      (node (ref "C3-12") (pin "C") (pinfunction "C_C") (pintype "passive"))
      (node (ref "C3-13") (pin "C") (pinfunction "C_C") (pintype "passive"))
      (node (ref "C3-14") (pin "C") (pinfunction "C_C") (pintype "passive"))
      (node (ref "C3-15") (pin "C") (pinfunction "C_C") (pintype "passive"))
      (node (ref "C3-9") (pin "C") (pinfunction "C_C") (pintype "passive"))
      (node (ref "C4-11") (pin "A") (pinfunction "A_A") (pintype "passive"))
      (node (ref "C5-11") (pin "A") (pinfunction "A_A") (pintype "passive"))
      (node (ref "C6-11") (pin "A") (pinfunction "A_A") (pintype "passive"))
      (node (ref "C7-11") (pin "A") (pinfunction "A_A") (pintype "passive"))
      (node (ref "C8-11") (pin "A") (pinfunction "A_A") (pintype "passive"))
      (node (ref "U1") (pin "9") (pinfunction "CB3_9") (pintype "bidirectional"))
    )
    (net (code "14") (name "/M_CB4") (class "Default")
      (node (ref "C2-11") (pin "A") (pinfunction "A_A") (pintype "passive"))
      (node (ref "C3-11") (pin "A") (pinfunction "A_A") (pintype "passive"))
      (node (ref "C4-10") (pin "C") (pinfunction "C_C") (pintype "passive"))
      (node (ref "C4-11") (pin "C") (pinfunction "C_C") (pintype "passive"))
      (node (ref "C4-12") (pin "C") (pinfunction "C_C") (pintype "passive"))
      (node (ref "C4-13") (pin "C") (pinfunction "C_C") (pintype "passive"))
      (node (ref "C4-14") (pin "C") (pinfunction "C_C") (pintype "passive"))
      (node (ref "C4-15") (pin "C") (pinfunction "C_C") (pintype "passive"))
      (node (ref "C4-9") (pin "C") (pinfunction "C_C") (pintype "passive"))
      (node (ref "C5-12") (pin "A") (pinfunction "A_A") (pintype "passive"))
      (node (ref "C6-12") (pin "A") (pinfunction "A_A") (pintype "passive"))
      (node (ref "C7-12") (pin "A") (pinfunction "A_A") (pintype "passive"))
      (node (ref "C8-12") (pin "A") (pinfunction "A_A") (pintype "passive"))
      (node (ref "U1") (pin "10") (pinfunction "CB4_10") (pintype "bidirectional"))
    )
    (net (code "15") (name "/M_CB5") (class "Default")
      (node (ref "C2-12") (pin "A") (pinfunction "A_A") (pintype "passive"))
      (node (ref "C3-12") (pin "A") (pinfunction "A_A") (pintype "passive"))
      (node (ref "C4-12") (pin "A") (pinfunction "A_A") (pintype "passive"))
      (node (ref "C5-10") (pin "C") (pinfunction "C_C") (pintype "passive"))
      (node (ref "C5-11") (pin "C") (pinfunction "C_C") (pintype "passive"))
      (node (ref "C5-12") (pin "C") (pinfunction "C_C") (pintype "passive"))
      (node (ref "C5-13") (pin "C") (pinfunction "C_C") (pintype "passive"))
      (node (ref "C5-14") (pin "C") (pinfunction "C_C") (pintype "passive"))
      (node (ref "C5-15") (pin "C") (pinfunction "C_C") (pintype "passive"))
      (node (ref "C5-9") (pin "C") (pinfunction "C_C") (pintype "passive"))
      (node (ref "C6-13") (pin "A") (pinfunction "A_A") (pintype "passive"))
      (node (ref "C7-13") (pin "A") (pinfunction "A_A") (pintype "passive"))
      (node (ref "C8-13") (pin "A") (pinfunction "A_A") (pintype "passive"))
      (node (ref "U1") (pin "11") (pinfunction "CB5_11") (pintype "bidirectional"))
    )
    (net (code "16") (name "/M_CB6") (class "Default")
      (node (ref "C2-13") (pin "A") (pinfunction "A_A") (pintype "passive"))
      (node (ref "C3-13") (pin "A") (pinfunction "A_A") (pintype "passive"))
      (node (ref "C4-13") (pin "A") (pinfunction "A_A") (pintype "passive"))
      (node (ref "C5-13") (pin "A") (pinfunction "A_A") (pintype "passive"))
      (node (ref "C6-10") (pin "C") (pinfunction "C_C") (pintype "passive"))
      (node (ref "C6-11") (pin "C") (pinfunction "C_C") (pintype "passive"))
      (node (ref "C6-12") (pin "C") (pinfunction "C_C") (pintype "passive"))
      (node (ref "C6-13") (pin "C") (pinfunction "C_C") (pintype "passive"))
      (node (ref "C6-14") (pin "C") (pinfunction "C_C") (pintype "passive"))
      (node (ref "C6-15") (pin "C") (pinfunction "C_C") (pintype "passive"))
      (node (ref "C6-9") (pin "C") (pinfunction "C_C") (pintype "passive"))
      (node (ref "C7-14") (pin "A") (pinfunction "A_A") (pintype "passive"))
      (node (ref "C8-14") (pin "A") (pinfunction "A_A") (pintype "passive"))
      (node (ref "U1") (pin "12") (pinfunction "CB6_12") (pintype "bidirectional"))
    )
    (net (code "17") (name "/M_CB7") (class "Default")
      (node (ref "C2-14") (pin "A") (pinfunction "A_A") (pintype "passive"))
      (node (ref "C3-14") (pin "A") (pinfunction "A_A") (pintype "passive"))
      (node (ref "C4-14") (pin "A") (pinfunction "A_A") (pintype "passive"))
      (node (ref "C5-14") (pin "A") (pinfunction "A_A") (pintype "passive"))
      (node (ref "C6-14") (pin "A") (pinfunction "A_A") (pintype "passive"))
      (node (ref "C7-10") (pin "C") (pinfunction "C_C") (pintype "passive"))
      (node (ref "C7-11") (pin "C") (pinfunction "C_C") (pintype "passive"))
      (node (ref "C7-12") (pin "C") (pinfunction "C_C") (pintype "passive"))
      (node (ref "C7-13") (pin "C") (pinfunction "C_C") (pintype "passive"))
      (node (ref "C7-14") (pin "C") (pinfunction "C_C") (pintype "passive"))
      (node (ref "C7-15") (pin "C") (pinfunction "C_C") (pintype "passive"))
      (node (ref "C7-9") (pin "C") (pinfunction "C_C") (pintype "passive"))
      (node (ref "C8-15") (pin "A") (pinfunction "A_A") (pintype "passive"))
      (node (ref "U1") (pin "13") (pinfunction "CB7_13") (pintype "bidirectional"))
    )
    (net (code "18") (name "/M_CB8") (class "Default")
      (node (ref "C2-15") (pin "A") (pinfunction "A_A") (pintype "passive"))
      (node (ref "C3-15") (pin "A") (pinfunction "A_A") (pintype "passive"))
      (node (ref "C4-15") (pin "A") (pinfunction "A_A") (pintype "passive"))
      (node (ref "C5-15") (pin "A") (pinfunction "A_A") (pintype "passive"))
      (node (ref "C6-15") (pin "A") (pinfunction "A_A") (pintype "passive"))
      (node (ref "C7-15") (pin "A") (pinfunction "A_A") (pintype "passive"))
      (node (ref "C8-10") (pin "C") (pinfunction "C_C") (pintype "passive"))
      (node (ref "C8-11") (pin "C") (pinfunction "C_C") (pintype "passive"))
      (node (ref "C8-12") (pin "C") (pinfunction "C_C") (pintype "passive"))
      (node (ref "C8-13") (pin "C") (pinfunction "C_C") (pintype "passive"))
      (node (ref "C8-14") (pin "C") (pinfunction "C_C") (pintype "passive"))
      (node (ref "C8-15") (pin "C") (pinfunction "C_C") (pintype "passive"))
      (node (ref "C8-9") (pin "C") (pinfunction "C_C") (pintype "passive"))
      (node (ref "U1") (pin "14") (pinfunction "CB8_14") (pintype "bidirectional"))
    )
    (net (code "19") (name "/M_INTB") (class "Default")
      (node (ref "U1") (pin "4") (pinfunction "INTB_4") (pintype "output"))
    )
    (net (code "20") (name "GND") (class "Default")
      (node (ref "C1") (pin "2") (pinfunction "2_2") (pintype "passive"))
      (node (ref "C2") (pin "2") (pinfunction "2_2") (pintype "passive"))
      (node (ref "C3") (pin "2") (pinfunction "2_2") (pintype "passive"))
      (node (ref "C4") (pin "2") (pinfunction "2_2") (pintype "passive"))
      (node (ref "C5") (pin "2") (pinfunction "2_2") (pintype "passive"))
      (node (ref "GND") (pin "TP") (pinfunction "TP_TP") (pintype "input"))
      (node (ref "K1") (pin "2") (pinfunction "2_2") (pintype "passive"))
      (node (ref "R7") (pin "2") (pinfunction "2_2") (pintype "passive"))
      (node (ref "R8") (pin "1") (pinfunction "1_1") (pintype "passive"))
      (node (ref "S1") (pin "1") (pinfunction "NO_1") (pintype "bidirectional"))
      (node (ref "S2") (pin "1") (pinfunction "NO_1") (pintype "bidirectional"))
      (node (ref "U1") (pin "5") (pinfunction "GND_5") (pintype "power_in"))
      (node (ref "U1") (pin "THERMAL") (pinfunction "GND_THERMAL") (pintype "power_in"))
    )
    (net (code "21") (name "M_SCL") (class "Default")
      (node (ref "K1") (pin "4") (pinfunction "4_4") (pintype "passive"))
      (node (ref "M_SCL") (pin "TP") (pinfunction "TP_TP") (pintype "input"))
      (node (ref "R6") (pin "1") (pinfunction "1_1") (pintype "passive"))
      (node (ref "U1") (pin "20") (pinfunction "SCL_20") (pintype "bidirectional"))
    )
    (net (code "22") (name "M_SDA") (class "Default")
      (node (ref "K1") (pin "3") (pinfunction "3_3") (pintype "passive"))
      (node (ref "M_SDA") (pin "TP") (pinfunction "TP_TP") (pintype "input"))
      (node (ref "R4") (pin "1") (pinfunction "1_1") (pintype "passive"))
      (node (ref "U1") (pin "19") (pinfunction "SDA_19") (pintype "bidirectional"))
    )
    (net (code "23") (name "Net-(S1-COM)") (class "Default")
      (node (ref "C2") (pin "1") (pinfunction "1_1") (pintype "passive"))
      (node (ref "R1") (pin "1") (pinfunction "1_1") (pintype "passive"))
      (node (ref "R3") (pin "1") (pinfunction "1_1") (pintype "passive"))
      (node (ref "S1") (pin "2") (pinfunction "COM_2") (pintype "bidirectional"))
    )
    (net (code "24") (name "Net-(S2-COM)") (class "Default")
      (node (ref "C3") (pin "1") (pinfunction "1_1") (pintype "passive"))
      (node (ref "R2") (pin "1") (pinfunction "1_1") (pintype "passive"))
      (node (ref "R5") (pin "1") (pinfunction "1_1") (pintype "passive"))
      (node (ref "S2") (pin "2") (pinfunction "COM_2") (pintype "bidirectional"))
    )
    (net (code "25") (name "Net-(U1-R_EXT)") (class "Default")
      (node (ref "R8") (pin "2") (pinfunction "2_2") (pintype "passive"))
      (node (ref "U1") (pin "6") (pinfunction "R_EXT_6") (pintype "bidirectional"))
    )
    (net (code "26") (name "S_DOWN") (class "Default")
      (node (ref "K1") (pin "6") (pinfunction "6_6") (pintype "passive"))
      (node (ref "R5") (pin "2") (pinfunction "2_2") (pintype "passive"))
      (node (ref "S_DOWN") (pin "TP") (pinfunction "TP_TP") (pintype "input"))
    )
    (net (code "27") (name "S_UP") (class "Default")
      (node (ref "K1") (pin "5") (pinfunction "5_5") (pintype "passive"))
      (node (ref "R3") (pin "2") (pinfunction "2_2") (pintype "passive"))
      (node (ref "S_UP") (pin "TP") (pinfunction "TP_TP") (pintype "input"))
    )
    (net (code "28") (name "VCC") (class "Default")
      (node (ref "C1") (pin "1") (pinfunction "1_1") (pintype "passive"))
      (node (ref "C4") (pin "1") (pinfunction "1_1") (pintype "passive"))
      (node (ref "C5") (pin "1") (pinfunction "1_1") (pintype "passive"))
      (node (ref "K1") (pin "1") (pinfunction "1_1") (pintype "passive"))
      (node (ref "R1") (pin "2") (pinfunction "2_2") (pintype "passive"))
      (node (ref "R2") (pin "2") (pinfunction "2_2") (pintype "passive"))
      (node (ref "R4") (pin "2") (pinfunction "2_2") (pintype "passive"))
      (node (ref "R6") (pin "2") (pinfunction "2_2") (pintype "passive"))
      (node (ref "U1") (pin "2") (pinfunction "VCC_2") (pintype "power_in"))
      (node (ref "U1") (pin "3") (pinfunction "SHUTDOWN_3") (pintype "input"))
      (node (ref "VCC") (pin "TP") (pinfunction "TP_TP") (pintype "input"))
    )
    (net (code "29") (name "unconnected-(U1-AUDIOIN-Pad17)") (class "Default")
      (node (ref "U1") (pin "17") (pinfunction "AUDIOIN_17") (pintype "input"))
    )
    (net (code "30") (name "unconnected-(U1-CB9-Pad15)") (class "Default")
      (node (ref "U1") (pin "15") (pinfunction "CB9_15") (pintype "bidirectional"))
    )
    (net (code "31") (name "unconnected-(U1-C_FILT-Pad16)") (class "Default")
      (node (ref "U1") (pin "16") (pinfunction "C_FILT_16") (pintype "bidirectional"))
    )
  )
)
